# PortBreakoutCapacitive_r4.net
KiCad netlist of a schematic drawn in EAGLE
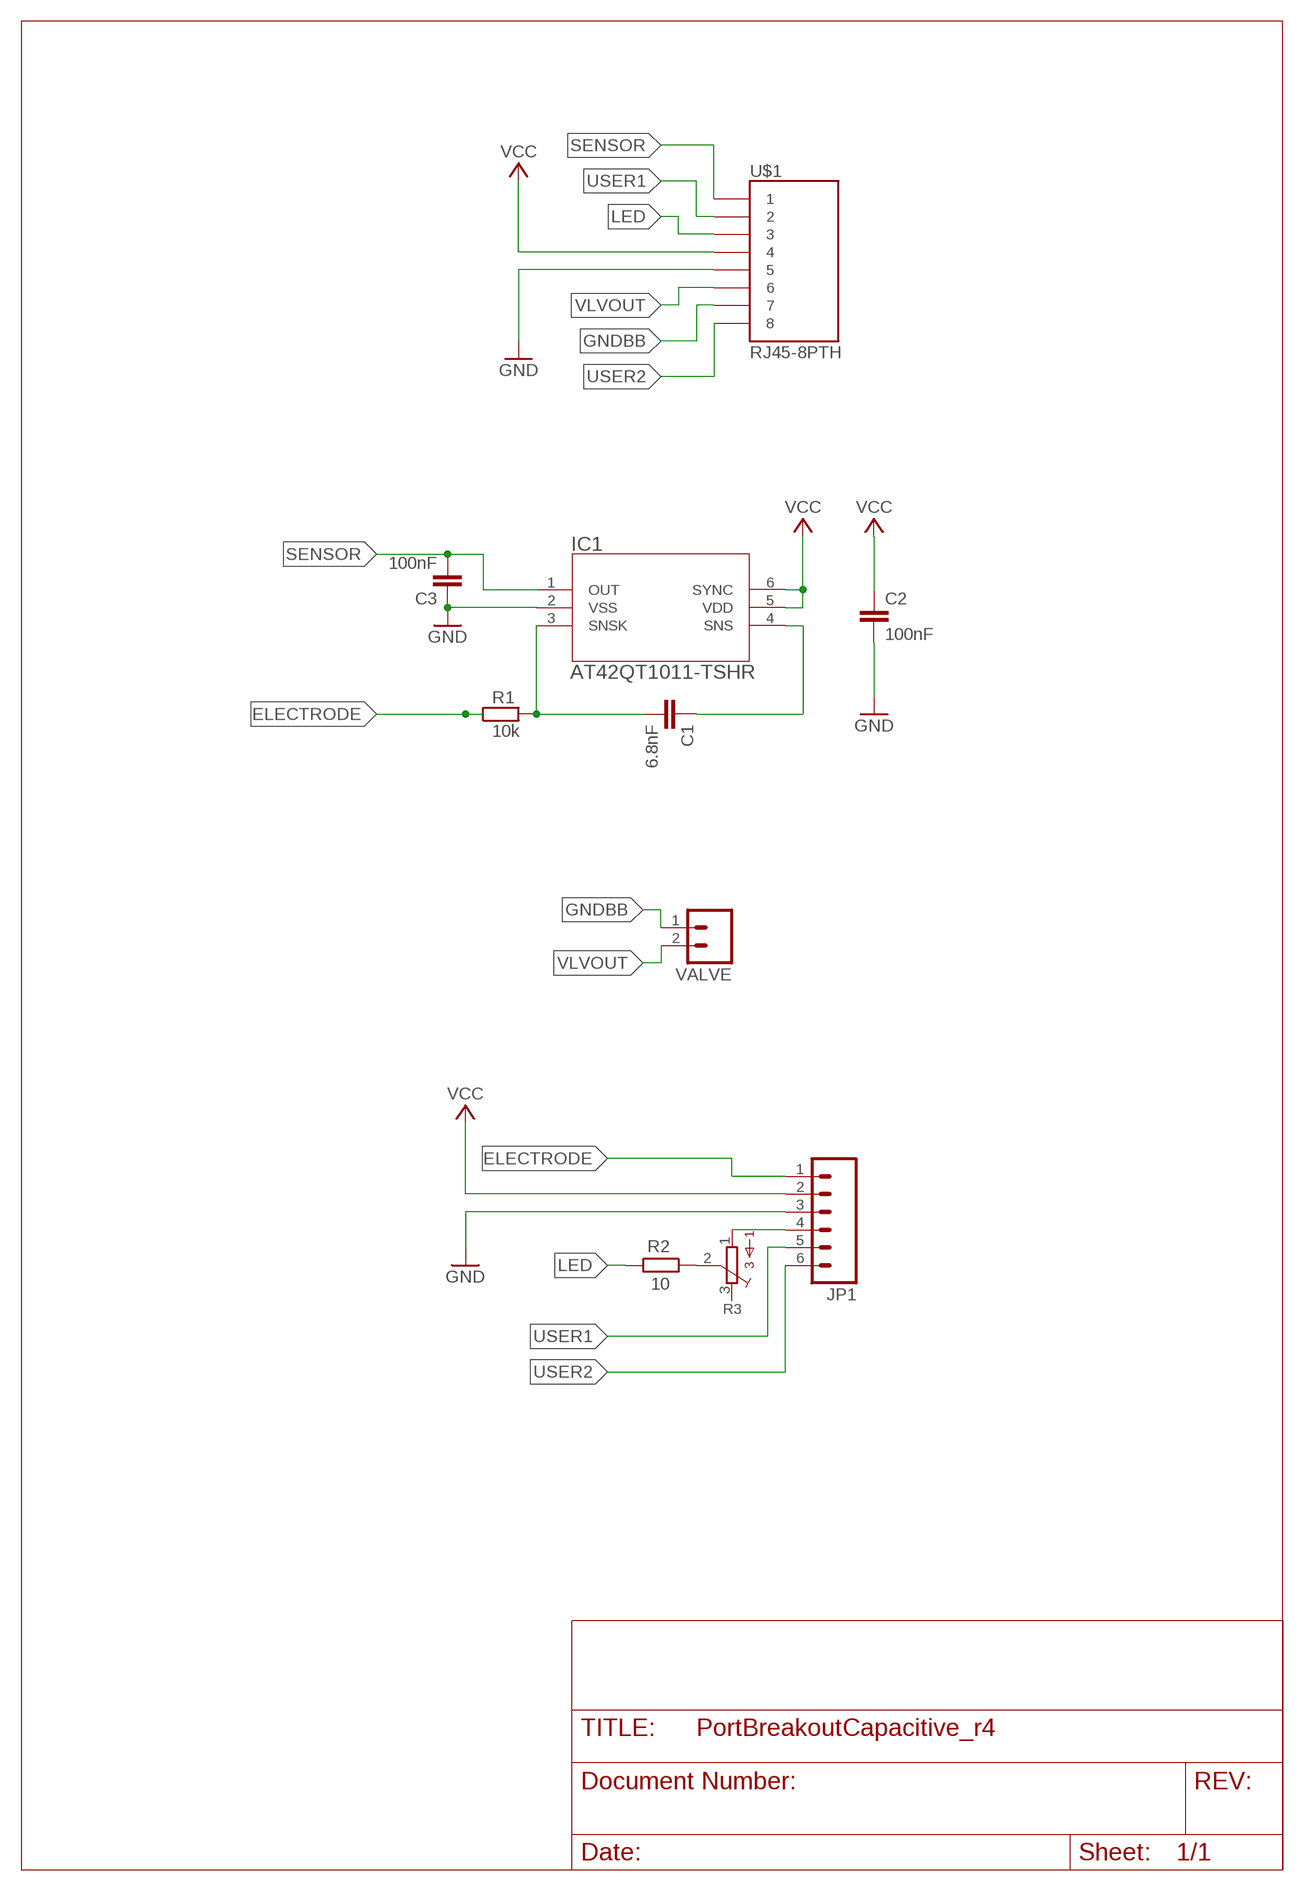
[diagram p0: schematic, sheet 1]

(export (version "E")
  (design (tool "Eeschema 10.0.6"))
  (components
    (comp (ref "C1")
      (value "6.8nF")
      (footprint "eagle-import:C1206")
      (libsource (lib "eagle-import") (part "C-EUC1206"))
    )
    (comp (ref "C2")
      (value "100nF")
      (footprint "eagle-import:C1206")
      (libsource (lib "eagle-import") (part "C-EUC1206"))
    )
    (comp (ref "C3")
      (value "100nF")
      (footprint "eagle-import:C1206")
      (libsource (lib "eagle-import") (part "C-EUC1206"))
    )
    (comp (ref "IC1")
      (value "AT42QT1011-TSHR")
      (footprint "eagle-import:6ST1_ATM")
      (fields (field (name "MANUFACTURER_PART_NUMBER") "AT42QT1010-TSHR"))
      (libsource (lib "eagle-import") (part "AT42QT1010-TSHR"))
    )
    (comp (ref "JP1")
      (value "M063.5MM-6")
      (footprint "eagle-import:SCREWTERMINAL-3.5MM-6")
      (libsource (lib "eagle-import") (part "M063.5MM-6"))
    )
    (comp (ref "R1")
      (value "10k")
      (footprint "eagle-import:R1206")
      (libsource (lib "eagle-import") (part "R-EU_R1206"))
    )
    (comp (ref "R2")
      (value "10")
      (footprint "eagle-import:R1206")
      (libsource (lib "eagle-import") (part "R-EU_R1206"))
    )
    (comp (ref "R3")
      (value "3362R")
      (footprint "eagle-import:3362R")
      (libsource (lib "eagle-import") (part "3362R"))
    )
    (comp (ref "U$1")
      (value "RJ45-8PTH")
      (footprint "eagle-import:RJ45-8")
      (libsource (lib "eagle-import") (part "RJ45-8PTH"))
    )
    (comp (ref "VALVE")
      (value "M023.5MM_LOCK")
      (footprint "eagle-import:SCREWTERMINAL-3.5MM-2_LOCK")
      (libsource (lib "eagle-import") (part "M023.5MM_LOCK"))
    )
  )
  (nets
    (net (code "1") (name "ELECTRODE") (class "Default")
      (node (ref "JP1") (pin "1") (pinfunction "1_1") (pintype "passive"))
      (node (ref "R1") (pin "1") (pinfunction "1_1") (pintype "passive"))
    )
    (net (code "2") (name "GND") (class "Default")
      (node (ref "C2") (pin "2") (pinfunction "2_2") (pintype "passive"))
      (node (ref "C3") (pin "1") (pinfunction "1_1") (pintype "passive"))
      (node (ref "IC1") (pin "2") (pinfunction "VSS_2") (pintype "power_in"))
      (node (ref "JP1") (pin "3") (pinfunction "3_3") (pintype "passive"))
      (node (ref "U$1") (pin "5") (pinfunction "5_5") (pintype "bidirectional"))
    )
    (net (code "3") (name "GNDBB") (class "Default")
      (node (ref "U$1") (pin "7") (pinfunction "7_7") (pintype "bidirectional"))
      (node (ref "VALVE") (pin "1") (pinfunction "1_1") (pintype "passive"))
    )
    (net (code "4") (name "LED") (class "Default")
      (node (ref "R2") (pin "2") (pinfunction "2_2") (pintype "passive"))
      (node (ref "U$1") (pin "3") (pinfunction "3_3") (pintype "bidirectional"))
    )
    (net (code "5") (name "Net-(IC1-SNS)") (class "Default")
      (node (ref "C1") (pin "1") (pinfunction "1_1") (pintype "passive"))
      (node (ref "IC1") (pin "4") (pinfunction "SNS_4") (pintype "bidirectional"))
    )
    (net (code "6") (name "Net-(IC1-SNSK)") (class "Default")
      (node (ref "C1") (pin "2") (pinfunction "2_2") (pintype "passive"))
      (node (ref "IC1") (pin "3") (pinfunction "SNSK_3") (pintype "bidirectional"))
      (node (ref "R1") (pin "2") (pinfunction "2_2") (pintype "passive"))
    )
    (net (code "7") (name "Net-(JP1-Pad4)") (class "Default")
      (node (ref "JP1") (pin "4") (pinfunction "4_4") (pintype "passive"))
      (node (ref "R3") (pin "1") (pinfunction "1_1") (pintype "passive"))
    )
    (net (code "8") (name "Net-(R2-Pad1)") (class "Default")
      (node (ref "R2") (pin "1") (pinfunction "1_1") (pintype "passive"))
      (node (ref "R3") (pin "2") (pinfunction "2_2") (pintype "passive"))
    )
    (net (code "9") (name "SENSOR") (class "Default")
      (node (ref "C3") (pin "2") (pinfunction "2_2") (pintype "passive"))
      (node (ref "IC1") (pin "1") (pinfunction "OUT_1") (pintype "output"))
      (node (ref "U$1") (pin "1") (pinfunction "1_1") (pintype "bidirectional"))
    )
    (net (code "10") (name "USER1") (class "Default")
      (node (ref "JP1") (pin "5") (pinfunction "5_5") (pintype "passive"))
      (node (ref "U$1") (pin "2") (pinfunction "2_2") (pintype "bidirectional"))
    )
    (net (code "11") (name "USER2") (class "Default")
      (node (ref "JP1") (pin "6") (pinfunction "6_6") (pintype "passive"))
      (node (ref "U$1") (pin "8") (pinfunction "8_8") (pintype "bidirectional"))
    )
    (net (code "12") (name "VCC") (class "Default")
      (node (ref "C2") (pin "1") (pinfunction "1_1") (pintype "passive"))
      (node (ref "IC1") (pin "5") (pinfunction "VDD_5") (pintype "power_in"))
      (node (ref "IC1") (pin "6") (pinfunction "SYNC_6") (pintype "input"))
      (node (ref "JP1") (pin "2") (pinfunction "2_2") (pintype "passive"))
      (node (ref "U$1") (pin "4") (pinfunction "4_4") (pintype "bidirectional"))
    )
    (net (code "13") (name "VLVOUT") (class "Default")
      (node (ref "U$1") (pin "6") (pinfunction "6_6") (pintype "bidirectional"))
      (node (ref "VALVE") (pin "2") (pinfunction "2_2") (pintype "passive"))
    )
    (net (code "14") (name "unconnected-(R3-Pad3)") (class "Default")
      (node (ref "R3") (pin "3") (pinfunction "3_3") (pintype "passive"))
    )
  )
)
